# integrated.net
KiCad netlist of a schematic drawn in EAGLE
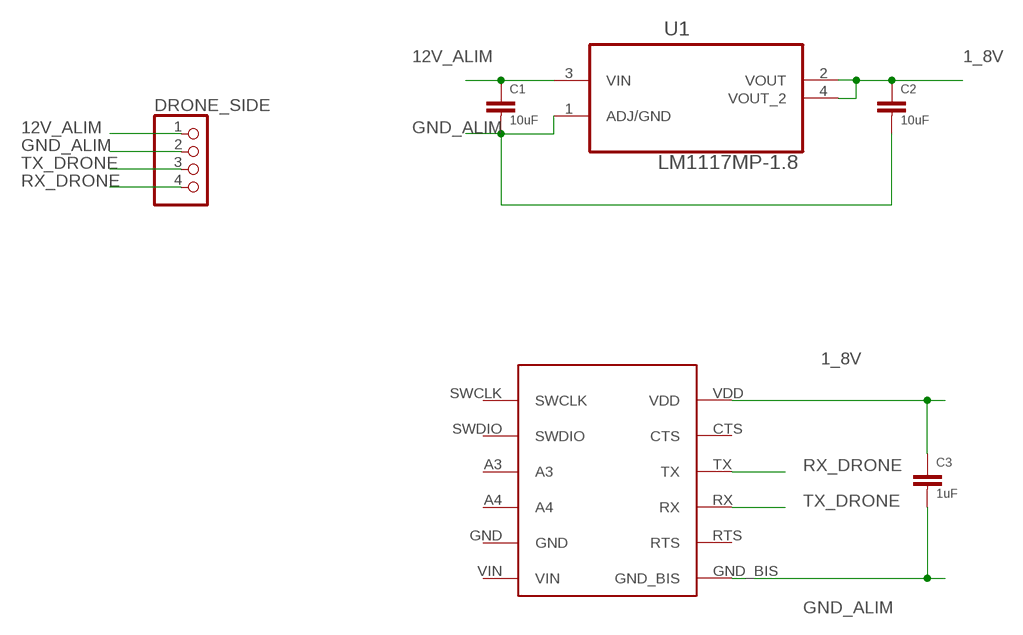
[diagram p0: schematic, sheet 1]

(export (version "E")
  (design (tool "Eeschema 10.0.6"))
  (components
    (comp (ref "C1")
      (value "10uF")
      (footprint "eagle-import:R0805")
      (libsource (lib "eagle-import") (part "C_0805"))
    )
    (comp (ref "C2")
      (value "10uF")
      (footprint "eagle-import:R0805")
      (libsource (lib "eagle-import") (part "C_0805"))
    )
    (comp (ref "C3")
      (value "1uF")
      (footprint "eagle-import:R1206")
      (libsource (lib "eagle-import") (part "C_1206"))
    )
    (comp (ref "DRONE_SIDE")
      (value "PINHD-1X4")
      (footprint "eagle-import:1X04")
      (libsource (lib "eagle-import") (part "PINHD-1X4"))
    )
    (comp (ref "U$2")
      (value "BLE_NANO")
      (footprint "eagle-import:MOUNTED_ON_PINHEADS")
      (libsource (lib "eagle-import") (part "BLE_NANO"))
    )
    (comp (ref "U1")
      (value "LM1117MP-1.8")
      (footprint "eagle-import:SOT230P696X180-4N")
      (libsource (lib "eagle-import") (part "LM1117MP-1.8"))
    )
  )
  (nets
    (net (code "1") (name "/1_8V") (class "Default")
      (node (ref "C2") (pin "1") (pinfunction "P$1_1") (pintype "passive"))
      (node (ref "C3") (pin "1") (pinfunction "P$1_1") (pintype "passive"))
      (node (ref "U$2") (pin "VDD") (pinfunction "VDD_VDD") (pintype "bidirectional"))
      (node (ref "U1") (pin "2") (pinfunction "VOUT_2") (pintype "output"))
      (node (ref "U1") (pin "4") (pinfunction "VOUT_2_4") (pintype "output"))
    )
    (net (code "2") (name "/12V_ALIM") (class "Default")
      (node (ref "C1") (pin "1") (pinfunction "P$1_1") (pintype "passive"))
      (node (ref "DRONE_SIDE") (pin "1") (pinfunction "1_1") (pintype "passive"))
      (node (ref "U1") (pin "3") (pinfunction "VIN_3") (pintype "input"))
    )
    (net (code "3") (name "/GND_ALIM") (class "Default")
      (node (ref "C1") (pin "2") (pinfunction "P$2_2") (pintype "passive"))
      (node (ref "C2") (pin "2") (pinfunction "P$2_2") (pintype "passive"))
      (node (ref "C3") (pin "2") (pinfunction "P$2_2") (pintype "passive"))
      (node (ref "DRONE_SIDE") (pin "2") (pinfunction "2_2") (pintype "passive"))
      (node (ref "U$2") (pin "GND_BIS") (pinfunction "GND_BIS_GND_BIS") (pintype "bidirectional"))
      (node (ref "U1") (pin "1") (pinfunction "ADJ/GND_1") (pintype "passive"))
    )
    (net (code "4") (name "/RX_DRONE") (class "Default")
      (node (ref "DRONE_SIDE") (pin "4") (pinfunction "4_4") (pintype "passive"))
      (node (ref "U$2") (pin "TX") (pinfunction "TX_TX") (pintype "bidirectional"))
    )
    (net (code "5") (name "/TX_DRONE") (class "Default")
      (node (ref "DRONE_SIDE") (pin "3") (pinfunction "3_3") (pintype "passive"))
      (node (ref "U$2") (pin "RX") (pinfunction "RX_RX") (pintype "bidirectional"))
    )
    (net (code "6") (name "unconnected-(U$2-PadA3)") (class "Default")
      (node (ref "U$2") (pin "A3") (pinfunction "A3_A3") (pintype "bidirectional"))
    )
    (net (code "7") (name "unconnected-(U$2-PadA4)") (class "Default")
      (node (ref "U$2") (pin "A4") (pinfunction "A4_A4") (pintype "bidirectional"))
    )
    (net (code "8") (name "unconnected-(U$2-PadCTS)") (class "Default")
      (node (ref "U$2") (pin "CTS") (pinfunction "CTS_CTS") (pintype "bidirectional"))
    )
    (net (code "9") (name "unconnected-(U$2-PadGND)") (class "Default")
      (node (ref "U$2") (pin "GND") (pinfunction "GND_GND") (pintype "bidirectional"))
    )
    (net (code "10") (name "unconnected-(U$2-PadRTS)") (class "Default")
      (node (ref "U$2") (pin "RTS") (pinfunction "RTS_RTS") (pintype "bidirectional"))
    )
    (net (code "11") (name "unconnected-(U$2-PadSWCLK)") (class "Default")
      (node (ref "U$2") (pin "SWCLK") (pinfunction "SWCLK_SWCLK") (pintype "bidirectional"))
    )
    (net (code "12") (name "unconnected-(U$2-PadSWDIO)") (class "Default")
      (node (ref "U$2") (pin "SWDIO") (pinfunction "SWDIO_SWDIO") (pintype "bidirectional"))
    )
    (net (code "13") (name "unconnected-(U$2-PadVIN)") (class "Default")
      (node (ref "U$2") (pin "VIN") (pinfunction "VIN_VIN") (pintype "bidirectional"))
    )
  )
)
